# Schematic.net
KiCad netlist of a schematic drawn in EasyEDA Pro
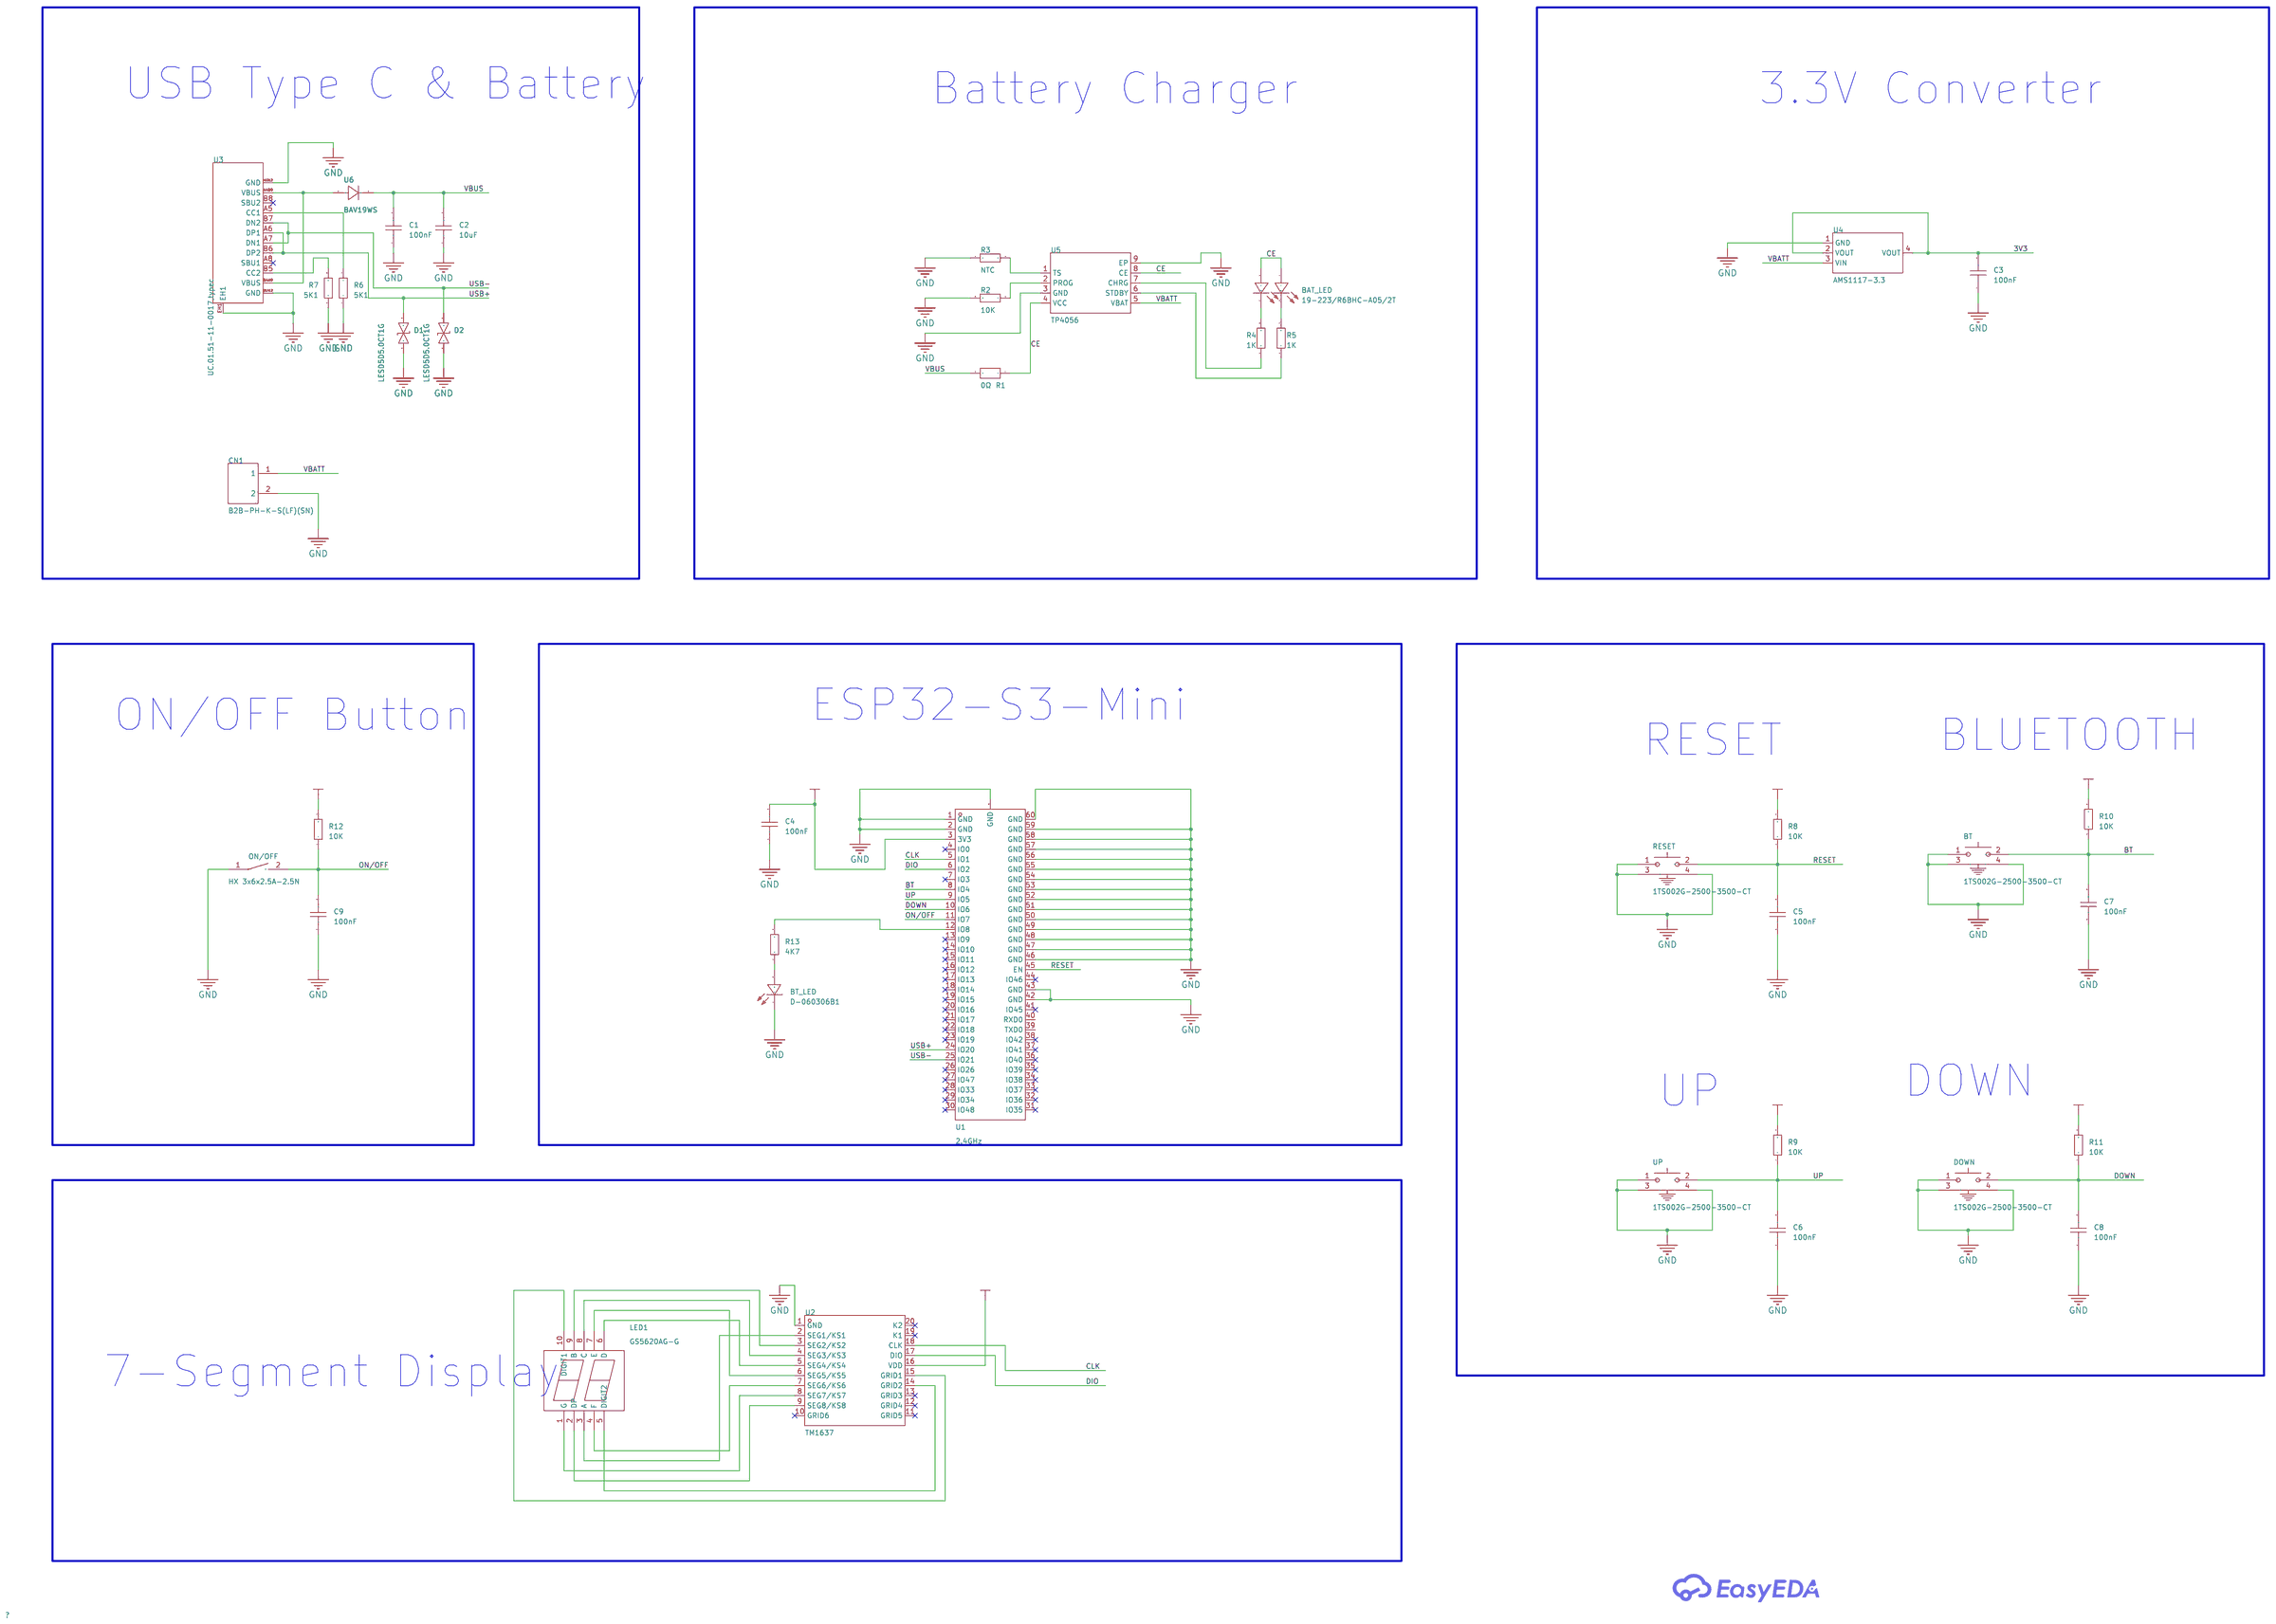
[diagram p0: schematic sheet]

(export (version "E")
  (design (tool "Eeschema 10.0.6"))
  (components
    (comp (ref "BAT_LED")
      (value "19-223/R6BHC-A05/2T")
      (footprint "easyedapro:LED-ARRAY-SMD_4P-L1.6-W1.3-BR-FD")
      (description "Emitted Color:Red,Blue")
      (fields (field (name "Manufacturer") "EVERLIGHT(亿光)"))
      (libsource (lib "easyedapro") (part "19-223/R6BHC-A05/2T"))
    )
    (comp (ref "BT")
      (value "1TS002G-2500-3500-CT")
      (footprint "easyedapro:SW-SMD_1TS002G-XXXX-3500-CT")
      (fields (field (name "Manufacturer") "HYP(鸿源精密)"))
      (libsource (lib "easyedapro") (part "1TS002G-2500-3500"))
    )
    (comp (ref "BT_LED")
      (value "D-060306B1")
      (footprint "easyedapro:LED0603-RD")
      (description "Emitted Color:Blue")
      (fields (field (name "Manufacturer") "ARKLED(方舟)"))
      (libsource (lib "easyedapro") (part "D-B060306B1-KS2"))
    )
    (comp (ref "C1")
      (value "100nF")
      (footprint "easyedapro:C0805")
      (description "Capacitance:100nF Tolerance:±10% Tolerance:±10% Voltage Rating:50V Temperature Coefficient:X7R")
      (fields
        (field (name "Manufacturer Part") "CSO0805X7R104K500KT")
        (field (name "Manufacturer") "HRE(芯声)")
      )
      (libsource (lib "easyedapro") (part "CSO0805X7R104K500KT"))
    )
    (comp (ref "C2")
      (value "10uF")
      (footprint "easyedapro:C0805")
      (description "Capacitance:10uF Tolerance:±10% Tolerance:±10% Voltage Rating:10V Temperature Coefficient:X5R")
      (fields
        (field (name "Manufacturer Part") "CL21A106KPCLQNC")
        (field (name "Manufacturer") "SAMSUNG(三星)")
      )
      (libsource (lib "easyedapro") (part "CL21A106KPCLQNC_C962097"))
    )
    (comp (ref "C3")
      (value "100nF")
      (footprint "easyedapro:C0805")
      (description "Capacitance:100nF Tolerance:±10% Tolerance:±10% Voltage Rating:50V Temperature Coefficient:X7R")
      (fields
        (field (name "Manufacturer Part") "CSO0805X7R104K500KT")
        (field (name "Manufacturer") "HRE(芯声)")
      )
      (libsource (lib "easyedapro") (part "CSO0805X7R104K500KT"))
    )
    (comp (ref "C4")
      (value "100nF")
      (footprint "easyedapro:C0805")
      (description "Capacitance:100nF Tolerance:±10% Tolerance:±10% Voltage Rating:50V Temperature Coefficient:X7R")
      (fields
        (field (name "Manufacturer Part") "CSO0805X7R104K500KT")
        (field (name "Manufacturer") "HRE(芯声)")
      )
      (libsource (lib "easyedapro") (part "CSO0805X7R104K500KT"))
    )
    (comp (ref "C5")
      (value "100nF")
      (footprint "easyedapro:C0805")
      (description "Capacitance:100nF Tolerance:±10% Tolerance:±10% Voltage Rating:50V Temperature Coefficient:X7R")
      (fields
        (field (name "Manufacturer Part") "CSO0805X7R104K500KT")
        (field (name "Manufacturer") "HRE(芯声)")
      )
      (libsource (lib "easyedapro") (part "CSO0805X7R104K500KT"))
    )
    (comp (ref "C6")
      (value "100nF")
      (footprint "easyedapro:C0805")
      (description "Capacitance:100nF Tolerance:±10% Tolerance:±10% Voltage Rating:50V Temperature Coefficient:X7R")
      (fields
        (field (name "Manufacturer Part") "CSO0805X7R104K500KT")
        (field (name "Manufacturer") "HRE(芯声)")
      )
      (libsource (lib "easyedapro") (part "CSO0805X7R104K500KT"))
    )
    (comp (ref "C7")
      (value "100nF")
      (footprint "easyedapro:C0805")
      (description "Capacitance:100nF Tolerance:±10% Tolerance:±10% Voltage Rating:50V Temperature Coefficient:X7R")
      (fields
        (field (name "Manufacturer Part") "CSO0805X7R104K500KT")
        (field (name "Manufacturer") "HRE(芯声)")
      )
      (libsource (lib "easyedapro") (part "CSO0805X7R104K500KT"))
    )
    (comp (ref "C8")
      (value "100nF")
      (footprint "easyedapro:C0805")
      (description "Capacitance:100nF Tolerance:±10% Tolerance:±10% Voltage Rating:50V Temperature Coefficient:X7R")
      (fields
        (field (name "Manufacturer Part") "CSO0805X7R104K500KT")
        (field (name "Manufacturer") "HRE(芯声)")
      )
      (libsource (lib "easyedapro") (part "CSO0805X7R104K500KT"))
    )
    (comp (ref "C9")
      (value "100nF")
      (footprint "easyedapro:C0805")
      (description "Capacitance:100nF Tolerance:±10% Tolerance:±10% Voltage Rating:50V Temperature Coefficient:X7R")
      (fields
        (field (name "Manufacturer Part") "CSO0805X7R104K500KT")
        (field (name "Manufacturer") "HRE(芯声)")
      )
      (libsource (lib "easyedapro") (part "CSO0805X7R104K500KT"))
    )
    (comp (ref "CN1")
      (value "B2B-PH-K-S(LF)(SN)")
      (footprint "easyedapro:CONN-TH_B2B-PH-K-S")
      (fields (field (name "Manufacturer") "JST"))
      (libsource (lib "easyedapro") (part "B2B-PH-K-S(LF)(SN)"))
    )
    (comp (ref "D1")
      (value "LESD5D5.0CT1G")
      (footprint "easyedapro:SOD-523_L1.2-W0.8-LS1.6-BI")
      (fields (field (name "Manufacturer") "LRC(乐山无线电)"))
      (libsource (lib "easyedapro") (part "LESD5D5.0CT1G"))
    )
    (comp (ref "D2")
      (value "LESD5D5.0CT1G")
      (footprint "easyedapro:SOD-523_L1.2-W0.8-LS1.6-BI")
      (fields (field (name "Manufacturer") "LRC(乐山无线电)"))
      (libsource (lib "easyedapro") (part "LESD5D5.0CT1G"))
    )
    (comp (ref "DOWN")
      (value "1TS002G-2500-3500-CT")
      (footprint "easyedapro:SW-SMD_1TS002G-XXXX-3500-CT")
      (fields (field (name "Manufacturer") "HYP(鸿源精密)"))
      (libsource (lib "easyedapro") (part "1TS002G-2500-3500"))
    )
    (comp (ref "LED1")
      (value "GS5620AG-G")
      (footprint "easyedapro:LED-SEG-SMD_10P-L25.1-W19.0-P2.54-S18.85-BL-1")
      (fields (field (name "Manufacturer") "Guangcai Display(光彩显示)"))
      (libsource (lib "easyedapro") (part "GS5620AG-G"))
    )
    (comp (ref "ON/OFF")
      (value "HX 3x6x2.5A-2.5N")
      (footprint "easyedapro:SW-SMD_HX-TS-1101-C-W")
      (fields (field (name "Manufacturer") "hanxia(韩下)"))
      (libsource (lib "easyedapro") (part "HX TS-1101-C-W"))
    )
    (comp (ref "R1")
      (value "0Ω")
      (footprint "easyedapro:R0603")
      (fields (field (name "Manufacturer Part") "PT0603-R-070RL") (field (name "Manufacturer") "YAGEO(国巨)"))
      (libsource (lib "easyedapro") (part "PT0603-R-070RL"))
    )
    (comp (ref "R2") (value "10K") (footprint "easyedapro:R0603") (libsource (lib "easyedapro") (part "Res")))
    (comp (ref "R3") (value "NTC") (footprint "easyedapro:R0603") (libsource (lib "easyedapro") (part "Res")))
    (comp (ref "R4") (value "1K") (footprint "easyedapro:R0603") (libsource (lib "easyedapro") (part "Res")))
    (comp (ref "R5") (value "1K") (footprint "easyedapro:R0603") (libsource (lib "easyedapro") (part "Res")))
    (comp (ref "R6") (value "5K1") (footprint "easyedapro:R0603") (libsource (lib "easyedapro") (part "Res")))
    (comp (ref "R7") (value "5K1") (footprint "easyedapro:R0603") (libsource (lib "easyedapro") (part "Res")))
    (comp (ref "R8") (value "10K") (footprint "easyedapro:R0603") (libsource (lib "easyedapro") (part "Res")))
    (comp (ref "R9") (value "10K") (footprint "easyedapro:R0603") (libsource (lib "easyedapro") (part "Res")))
    (comp (ref "R10")
      (value "10K")
      (footprint "easyedapro:R0603")
      (libsource (lib "easyedapro") (part "Res"))
    )
    (comp (ref "R11")
      (value "10K")
      (footprint "easyedapro:R0603")
      (libsource (lib "easyedapro") (part "Res"))
    )
    (comp (ref "R12")
      (value "10K")
      (footprint "easyedapro:R0603")
      (libsource (lib "easyedapro") (part "Res"))
    )
    (comp (ref "R13")
      (value "4K7")
      (footprint "easyedapro:R0603")
      (libsource (lib "easyedapro") (part "Res"))
    )
    (comp (ref "RESET")
      (value "1TS002G-2500-3500-CT")
      (footprint "easyedapro:SW-SMD_1TS002G-XXXX-3500-CT")
      (fields (field (name "Manufacturer") "HYP(鸿源精密)"))
      (libsource (lib "easyedapro") (part "1TS002G-2500-3500"))
    )
    (comp (ref "U1")
      (value "2.4GHz")
      (footprint "easyedapro:BULETM-SMD_ESP32-S3-MINI-1-N8")
      (fields
        (field (name "Manufacturer Part") "ESP32-S3-MINI-1-N8")
        (field (name "Manufacturer") "ESPRESSIF(乐鑫)")
      )
      (libsource (lib "easyedapro") (part "ESP32-S3-MINI-1-N8"))
    )
    (comp (ref "U2")
      (value "TM1637")
      (footprint "easyedapro:SOP-20_L12.8-W7.5-P1.27-LS10.4-BL")
      (fields (field (name "Manufacturer") "TM(天微)"))
      (libsource (lib "easyedapro") (part "TM1637_C2962580"))
    )
    (comp (ref "U3")
      (value "UC.01.51-11-0017,typec")
      (footprint "easyedapro:TYPE-C-SMD_UC.01.51-11-0017")
      (libsource (lib "easyedapro") (part "UC.01.51-11-0017,TYPEC"))
    )
    (comp (ref "U4")
      (value "AMS1117-3.3")
      (footprint "easyedapro:SOT-223-3_L6.5-W3.4-P2.30-LS7.0-BR")
      (fields (field (name "Manufacturer") "AMS"))
      (libsource (lib "easyedapro") (part "AMS1117-3.3"))
    )
    (comp (ref "U5")
      (value "TP4056")
      (footprint "easyedapro:ESOP-8_L4.9-W3.9-P1.27-LS6.0-BL-EP")
      (fields (field (name "Manufacturer") "JSMSEMI(杰盛微)"))
      (libsource (lib "easyedapro") (part "TP4056_C22470410"))
    )
    (comp (ref "U6")
      (value "BAV19WS")
      (footprint "easyedapro:SOD-323_L1.8-W1.3-LS2.5-RD-1")
      (fields (field (name "Manufacturer") "XZT(信展通)"))
      (libsource (lib "easyedapro") (part "BAV19WS_C5805720"))
    )
    (comp (ref "UP")
      (value "1TS002G-2500-3500-CT")
      (footprint "easyedapro:SW-SMD_1TS002G-XXXX-3500-CT")
      (fields (field (name "Manufacturer") "HYP(鸿源精密)"))
      (libsource (lib "easyedapro") (part "1TS002G-2500-3500"))
    )
  )
  (nets
    (net (code "1") (name "/BT") (class "Default")
      (node (ref "BT") (pin "2") (pinfunction "2_2") (pintype "input"))
      (node (ref "C7") (pin "2") (pinfunction "2_2") (pintype "unspecified"))
      (node (ref "R10") (pin "1") (pinfunction "1_1") (pintype "input"))
      (node (ref "U1") (pin "8") (pinfunction "IO4_8") (pintype "unspecified"))
    )
    (net (code "2") (name "/CE") (class "Default")
      (node (ref "BAT_LED") (pin "1") (pinfunction "A_1") (pintype "unspecified"))
      (node (ref "BAT_LED") (pin "3") (pinfunction "A_3") (pintype "unspecified"))
      (node (ref "R1") (pin "1") (pinfunction "1_1") (pintype "unspecified"))
      (node (ref "U5") (pin "4") (pinfunction "VCC_4") (pintype "unspecified"))
      (node (ref "U5") (pin "8") (pinfunction "CE_8") (pintype "unspecified"))
    )
    (net (code "3") (name "/CLK") (class "Default")
      (node (ref "U1") (pin "5") (pinfunction "IO1_5") (pintype "unspecified"))
      (node (ref "U2") (pin "18") (pinfunction "CLK_18") (pintype "unspecified"))
    )
    (net (code "4") (name "/DIO") (class "Default")
      (node (ref "U1") (pin "6") (pinfunction "IO2_6") (pintype "unspecified"))
      (node (ref "U2") (pin "17") (pinfunction "DIO_17") (pintype "unspecified"))
    )
    (net (code "5") (name "/DOWN") (class "Default")
      (node (ref "C8") (pin "2") (pinfunction "2_2") (pintype "unspecified"))
      (node (ref "DOWN") (pin "2") (pinfunction "2_2") (pintype "input"))
      (node (ref "R11") (pin "1") (pinfunction "1_1") (pintype "input"))
      (node (ref "U1") (pin "10") (pinfunction "IO6_10") (pintype "unspecified"))
    )
    (net (code "6") (name "/ON{slash}OFF") (class "Default")
      (node (ref "C9") (pin "2") (pinfunction "2_2") (pintype "unspecified"))
      (node (ref "ON/OFF") (pin "2") (pinfunction "2_2") (pintype "unspecified"))
      (node (ref "R12") (pin "1") (pinfunction "1_1") (pintype "input"))
      (node (ref "U1") (pin "11") (pinfunction "IO7_11") (pintype "unspecified"))
    )
    (net (code "7") (name "/RESET") (class "Default")
      (node (ref "C5") (pin "2") (pinfunction "2_2") (pintype "unspecified"))
      (node (ref "R8") (pin "1") (pinfunction "1_1") (pintype "input"))
      (node (ref "RESET") (pin "2") (pinfunction "2_2") (pintype "input"))
      (node (ref "U1") (pin "45") (pinfunction "EN_45") (pintype "unspecified"))
    )
    (net (code "8") (name "/UP") (class "Default")
      (node (ref "C6") (pin "2") (pinfunction "2_2") (pintype "unspecified"))
      (node (ref "R9") (pin "1") (pinfunction "1_1") (pintype "input"))
      (node (ref "U1") (pin "9") (pinfunction "IO5_9") (pintype "unspecified"))
      (node (ref "UP") (pin "2") (pinfunction "2_2") (pintype "input"))
    )
    (net (code "9") (name "/USB+") (class "Default")
      (node (ref "D1") (pin "2") (pinfunction "2_2") (pintype "unspecified"))
      (node (ref "U1") (pin "24") (pinfunction "IO20_24") (pintype "unspecified"))
      (node (ref "U3") (pin "A6") (pinfunction "DP1_A6") (pintype "unspecified"))
      (node (ref "U3") (pin "B6") (pinfunction "DP2_B6") (pintype "unspecified"))
    )
    (net (code "10") (name "/USB-") (class "Default")
      (node (ref "D2") (pin "2") (pinfunction "2_2") (pintype "unspecified"))
      (node (ref "U1") (pin "25") (pinfunction "IO21_25") (pintype "unspecified"))
      (node (ref "U3") (pin "A7") (pinfunction "DN1_A7") (pintype "unspecified"))
      (node (ref "U3") (pin "B7") (pinfunction "DN2_B7") (pintype "unspecified"))
    )
    (net (code "11") (name "/VBUS") (class "Default")
      (node (ref "C1") (pin "2") (pinfunction "2_2") (pintype "unspecified"))
      (node (ref "C2") (pin "2") (pinfunction "2_2") (pintype "unspecified"))
      (node (ref "R1") (pin "2") (pinfunction "2_2") (pintype "unspecified"))
      (node (ref "U6") (pin "1") (pinfunction "K_1") (pintype "unspecified"))
    )
    (net (code "12") (name "3V3") (class "Default")
      (node (ref "C3") (pin "2") (pinfunction "2_2") (pintype "unspecified"))
      (node (ref "C4") (pin "2") (pinfunction "2_2") (pintype "unspecified"))
      (node (ref "R10") (pin "2") (pinfunction "2_2") (pintype "input"))
      (node (ref "R11") (pin "2") (pinfunction "2_2") (pintype "input"))
      (node (ref "R12") (pin "2") (pinfunction "2_2") (pintype "input"))
      (node (ref "R8") (pin "2") (pinfunction "2_2") (pintype "input"))
      (node (ref "R9") (pin "2") (pinfunction "2_2") (pintype "input"))
      (node (ref "U1") (pin "3") (pinfunction "3V3_3") (pintype "unspecified"))
      (node (ref "U4") (pin "2") (pinfunction "VOUT_2") (pintype "unspecified"))
      (node (ref "U4") (pin "4") (pinfunction "VOUT_4") (pintype "unspecified"))
    )
    (net (code "13") (name "GND") (class "Default")
      (node (ref "BT") (pin "1") (pinfunction "1_1") (pintype "input"))
      (node (ref "BT") (pin "3") (pinfunction "3_3") (pintype "input"))
      (node (ref "BT") (pin "4") (pinfunction "4_4") (pintype "input"))
      (node (ref "BT_LED") (pin "1") (pinfunction "1_1") (pintype "unspecified"))
      (node (ref "C1") (pin "1") (pinfunction "1_1") (pintype "unspecified"))
      (node (ref "C2") (pin "1") (pinfunction "1_1") (pintype "unspecified"))
      (node (ref "C3") (pin "1") (pinfunction "1_1") (pintype "unspecified"))
      (node (ref "C4") (pin "1") (pinfunction "1_1") (pintype "unspecified"))
      (node (ref "C5") (pin "1") (pinfunction "1_1") (pintype "unspecified"))
      (node (ref "C6") (pin "1") (pinfunction "1_1") (pintype "unspecified"))
      (node (ref "C7") (pin "1") (pinfunction "1_1") (pintype "unspecified"))
      (node (ref "C8") (pin "1") (pinfunction "1_1") (pintype "unspecified"))
      (node (ref "C9") (pin "1") (pinfunction "1_1") (pintype "unspecified"))
      (node (ref "CN1") (pin "2") (pinfunction "2_2") (pintype "input"))
      (node (ref "D1") (pin "1") (pinfunction "1_1") (pintype "unspecified"))
      (node (ref "D2") (pin "1") (pinfunction "1_1") (pintype "unspecified"))
      (node (ref "DOWN") (pin "1") (pinfunction "1_1") (pintype "input"))
      (node (ref "DOWN") (pin "3") (pinfunction "3_3") (pintype "input"))
      (node (ref "DOWN") (pin "4") (pinfunction "4_4") (pintype "input"))
      (node (ref "ON/OFF") (pin "1") (pinfunction "1_1") (pintype "unspecified"))
      (node (ref "R2") (pin "2") (pinfunction "2_2") (pintype "input"))
      (node (ref "R3") (pin "1") (pinfunction "1_1") (pintype "input"))
      (node (ref "R6") (pin "1") (pinfunction "1_1") (pintype "input"))
      (node (ref "R7") (pin "1") (pinfunction "1_1") (pintype "input"))
      (node (ref "RESET") (pin "1") (pinfunction "1_1") (pintype "input"))
      (node (ref "RESET") (pin "3") (pinfunction "3_3") (pintype "input"))
      (node (ref "RESET") (pin "4") (pinfunction "4_4") (pintype "input"))
      (node (ref "U1") (pin "1") (pinfunction "GND_1") (pintype "unspecified"))
      (node (ref "U1") (pin "2") (pinfunction "GND_2") (pintype "unspecified"))
      (node (ref "U1") (pin "42") (pinfunction "GND_42") (pintype "unspecified"))
      (node (ref "U1") (pin "43") (pinfunction "GND_43") (pintype "unspecified"))
      (node (ref "U1") (pin "46") (pinfunction "GND_46") (pintype "unspecified"))
      (node (ref "U1") (pin "47") (pinfunction "GND_47") (pintype "unspecified"))
      (node (ref "U1") (pin "48") (pinfunction "GND_48") (pintype "unspecified"))
      (node (ref "U1") (pin "49") (pinfunction "GND_49") (pintype "unspecified"))
      (node (ref "U1") (pin "50") (pinfunction "GND_50") (pintype "unspecified"))
      (node (ref "U1") (pin "51") (pinfunction "GND_51") (pintype "unspecified"))
      (node (ref "U1") (pin "52") (pinfunction "GND_52") (pintype "unspecified"))
      (node (ref "U1") (pin "53") (pinfunction "GND_53") (pintype "unspecified"))
      (node (ref "U1") (pin "54") (pinfunction "GND_54") (pintype "unspecified"))
      (node (ref "U1") (pin "55") (pinfunction "GND_55") (pintype "unspecified"))
      (node (ref "U1") (pin "56") (pinfunction "GND_56") (pintype "unspecified"))
      (node (ref "U1") (pin "57") (pinfunction "GND_57") (pintype "unspecified"))
      (node (ref "U1") (pin "58") (pinfunction "GND_58") (pintype "unspecified"))
      (node (ref "U1") (pin "59") (pinfunction "GND_59") (pintype "unspecified"))
      (node (ref "U1") (pin "60") (pinfunction "GND_60") (pintype "unspecified"))
      (node (ref "U1") (pin "GND") (pinfunction "GND_GND") (pintype "unspecified"))
      (node (ref "U2") (pin "1") (pinfunction "GND_1") (pintype "unspecified"))
      (node (ref "U3") (pin "A1B12") (pinfunction "GND_A1B12") (pintype "unspecified"))
      (node (ref "U3") (pin "B1A12") (pinfunction "GND_B1A12") (pintype "unspecified"))
      (node (ref "U3") (pin "EH1") (pinfunction "EH1_EH1") (pintype "unspecified"))
      (node (ref "U4") (pin "1") (pinfunction "GND_1") (pintype "unspecified"))
      (node (ref "U5") (pin "3") (pinfunction "GND_3") (pintype "unspecified"))
      (node (ref "U5") (pin "9") (pinfunction "EP_9") (pintype "unspecified"))
      (node (ref "UP") (pin "1") (pinfunction "1_1") (pintype "input"))
      (node (ref "UP") (pin "3") (pinfunction "3_3") (pintype "input"))
      (node (ref "UP") (pin "4") (pinfunction "4_4") (pintype "input"))
    )
    (net (code "14") (name "Net-(BAT_LED-C-Pad2)") (class "Default")
      (node (ref "BAT_LED") (pin "2") (pinfunction "C_2") (pintype "unspecified"))
      (node (ref "R5") (pin "2") (pinfunction "2_2") (pintype "input"))
    )
    (net (code "15") (name "Net-(BAT_LED-C-Pad4)") (class "Default")
      (node (ref "BAT_LED") (pin "4") (pinfunction "C_4") (pintype "unspecified"))
      (node (ref "R4") (pin "2") (pinfunction "2_2") (pintype "input"))
    )
    (net (code "16") (name "Net-(BT_LED-Pad2)") (class "Default")
      (node (ref "BT_LED") (pin "2") (pinfunction "2_2") (pintype "unspecified"))
      (node (ref "R13") (pin "1") (pinfunction "1_1") (pintype "input"))
    )
    (net (code "17") (name "Net-(LED1-A)") (class "Default")
      (node (ref "LED1") (pin "3") (pinfunction "A_3") (pintype "unspecified"))
      (node (ref "U2") (pin "2") (pinfunction "SEG1/KS1_2") (pintype "unspecified"))
    )
    (net (code "18") (name "Net-(LED1-B)") (class "Default")
      (node (ref "LED1") (pin "9") (pinfunction "B_9") (pintype "unspecified"))
      (node (ref "U2") (pin "3") (pinfunction "SEG2/KS2_3") (pintype "unspecified"))
    )
    (net (code "19") (name "Net-(LED1-C)") (class "Default")
      (node (ref "LED1") (pin "8") (pinfunction "C_8") (pintype "unspecified"))
      (node (ref "U2") (pin "4") (pinfunction "SEG3/KS3_4") (pintype "unspecified"))
    )
    (net (code "20") (name "Net-(LED1-D)") (class "Default")
      (node (ref "LED1") (pin "6") (pinfunction "D_6") (pintype "unspecified"))
      (node (ref "U2") (pin "5") (pinfunction "SEG4/KS4_5") (pintype "unspecified"))
    )
    (net (code "21") (name "Net-(LED1-DIGIT1)") (class "Default")
      (node (ref "LED1") (pin "10") (pinfunction "DIGIT1_10") (pintype "unspecified"))
      (node (ref "U2") (pin "15") (pinfunction "GRID1_15") (pintype "unspecified"))
    )
    (net (code "22") (name "Net-(LED1-DIGIT2)") (class "Default")
      (node (ref "LED1") (pin "5") (pinfunction "DIGIT2_5") (pintype "unspecified"))
      (node (ref "U2") (pin "14") (pinfunction "GRID2_14") (pintype "unspecified"))
    )
    (net (code "23") (name "Net-(LED1-DP)") (class "Default")
      (node (ref "LED1") (pin "2") (pinfunction "DP_2") (pintype "unspecified"))
      (node (ref "U2") (pin "9") (pinfunction "SEG8/KS8_9") (pintype "unspecified"))
    )
    (net (code "24") (name "Net-(LED1-E)") (class "Default")
      (node (ref "LED1") (pin "7") (pinfunction "E_7") (pintype "unspecified"))
      (node (ref "U2") (pin "6") (pinfunction "SEG5/KS5_6") (pintype "unspecified"))
    )
    (net (code "25") (name "Net-(LED1-F)") (class "Default")
      (node (ref "LED1") (pin "4") (pinfunction "F_4") (pintype "unspecified"))
      (node (ref "U2") (pin "7") (pinfunction "SEG6/KS6_7") (pintype "unspecified"))
    )
    (net (code "26") (name "Net-(LED1-G)") (class "Default")
      (node (ref "LED1") (pin "1") (pinfunction "G_1") (pintype "unspecified"))
      (node (ref "U2") (pin "8") (pinfunction "SEG7/KS7_8") (pintype "unspecified"))
    )
    (net (code "27") (name "Net-(U1-IO8)") (class "Default")
      (node (ref "R13") (pin "2") (pinfunction "2_2") (pintype "input"))
      (node (ref "U1") (pin "12") (pinfunction "IO8_12") (pintype "unspecified"))
    )
    (net (code "28") (name "Net-(U3-CC1)") (class "Default")
      (node (ref "R6") (pin "2") (pinfunction "2_2") (pintype "input"))
      (node (ref "U3") (pin "A5") (pinfunction "CC1_A5") (pintype "unspecified"))
    )
    (net (code "29") (name "Net-(U3-CC2)") (class "Default")
      (node (ref "R7") (pin "2") (pinfunction "2_2") (pintype "input"))
      (node (ref "U3") (pin "B5") (pinfunction "CC2_B5") (pintype "unspecified"))
    )
    (net (code "30") (name "Net-(U5-CHRG)") (class "Default")
      (node (ref "R4") (pin "1") (pinfunction "1_1") (pintype "input"))
      (node (ref "U5") (pin "7") (pinfunction "CHRG_7") (pintype "unspecified"))
    )
    (net (code "31") (name "Net-(U5-PROG)") (class "Default")
      (node (ref "R2") (pin "1") (pinfunction "1_1") (pintype "input"))
      (node (ref "U5") (pin "2") (pinfunction "PROG_2") (pintype "unspecified"))
    )
    (net (code "32") (name "Net-(U5-STDBY)") (class "Default")
      (node (ref "R5") (pin "1") (pinfunction "1_1") (pintype "input"))
      (node (ref "U5") (pin "6") (pinfunction "STDBY_6") (pintype "unspecified"))
    )
    (net (code "33") (name "Net-(U5-TS)") (class "Default")
      (node (ref "R3") (pin "2") (pinfunction "2_2") (pintype "input"))
      (node (ref "U5") (pin "1") (pinfunction "TS_1") (pintype "unspecified"))
    )
    (net (code "34") (name "Net-(U6-A)") (class "Default")
      (node (ref "U3") (pin "A4B9") (pinfunction "VBUS_A4B9") (pintype "unspecified"))
      (node (ref "U3") (pin "B4A9") (pinfunction "VBUS_B4A9") (pintype "unspecified"))
      (node (ref "U6") (pin "2") (pinfunction "A_2") (pintype "unspecified"))
    )
    (net (code "35") (name "VBATT") (class "Default")
      (node (ref "CN1") (pin "1") (pinfunction "1_1") (pintype "input"))
      (node (ref "U2") (pin "16") (pinfunction "VDD_16") (pintype "unspecified"))
      (node (ref "U4") (pin "3") (pinfunction "VIN_3") (pintype "unspecified"))
      (node (ref "U5") (pin "5") (pinfunction "VBAT_5") (pintype "unspecified"))
    )
    (net (code "36") (name "unconnected-(U1-IO0-Pad4)") (class "Default")
      (node (ref "U1") (pin "4") (pinfunction "IO0_4") (pintype "unspecified+no_connect"))
    )
    (net (code "37") (name "unconnected-(U1-IO3-Pad7)") (class "Default")
      (node (ref "U1") (pin "7") (pinfunction "IO3_7") (pintype "unspecified+no_connect"))
    )
    (net (code "38") (name "unconnected-(U1-IO9-Pad13)") (class "Default")
      (node (ref "U1") (pin "13") (pinfunction "IO9_13") (pintype "unspecified+no_connect"))
    )
    (net (code "39") (name "unconnected-(U1-IO10-Pad14)") (class "Default")
      (node (ref "U1") (pin "14") (pinfunction "IO10_14") (pintype "unspecified+no_connect"))
    )
    (net (code "40") (name "unconnected-(U1-IO11-Pad15)") (class "Default")
      (node (ref "U1") (pin "15") (pinfunction "IO11_15") (pintype "unspecified+no_connect"))
    )
    (net (code "41") (name "unconnected-(U1-IO12-Pad16)") (class "Default")
      (node (ref "U1") (pin "16") (pinfunction "IO12_16") (pintype "unspecified+no_connect"))
    )
    (net (code "42") (name "unconnected-(U1-IO13-Pad17)") (class "Default")
      (node (ref "U1") (pin "17") (pinfunction "IO13_17") (pintype "unspecified+no_connect"))
    )
    (net (code "43") (name "unconnected-(U1-IO14-Pad18)") (class "Default")
      (node (ref "U1") (pin "18") (pinfunction "IO14_18") (pintype "unspecified+no_connect"))
    )
    (net (code "44") (name "unconnected-(U1-IO15-Pad19)") (class "Default")
      (node (ref "U1") (pin "19") (pinfunction "IO15_19") (pintype "unspecified+no_connect"))
    )
    (net (code "45") (name "unconnected-(U1-IO16-Pad20)") (class "Default")
      (node (ref "U1") (pin "20") (pinfunction "IO16_20") (pintype "unspecified+no_connect"))
    )
    (net (code "46") (name "unconnected-(U1-IO17-Pad21)") (class "Default")
      (node (ref "U1") (pin "21") (pinfunction "IO17_21") (pintype "unspecified+no_connect"))
    )
    (net (code "47") (name "unconnected-(U1-IO18-Pad22)") (class "Default")
      (node (ref "U1") (pin "22") (pinfunction "IO18_22") (pintype "unspecified+no_connect"))
    )
    (net (code "48") (name "unconnected-(U1-IO19-Pad23)") (class "Default")
      (node (ref "U1") (pin "23") (pinfunction "IO19_23") (pintype "unspecified+no_connect"))
    )
    (net (code "49") (name "unconnected-(U1-IO26-Pad26)") (class "Default")
      (node (ref "U1") (pin "26") (pinfunction "IO26_26") (pintype "unspecified+no_connect"))
    )
    (net (code "50") (name "unconnected-(U1-IO33-Pad28)") (class "Default")
      (node (ref "U1") (pin "28") (pinfunction "IO33_28") (pintype "unspecified+no_connect"))
    )
    (net (code "51") (name "unconnected-(U1-IO34-Pad29)") (class "Default")
      (node (ref "U1") (pin "29") (pinfunction "IO34_29") (pintype "unspecified+no_connect"))
    )
    (net (code "52") (name "unconnected-(U1-IO35-Pad31)") (class "Default")
      (node (ref "U1") (pin "31") (pinfunction "IO35_31") (pintype "unspecified+no_connect"))
    )
    (net (code "53") (name "unconnected-(U1-IO36-Pad32)") (class "Default")
      (node (ref "U1") (pin "32") (pinfunction "IO36_32") (pintype "unspecified+no_connect"))
    )
    (net (code "54") (name "unconnected-(U1-IO37-Pad33)") (class "Default")
      (node (ref "U1") (pin "33") (pinfunction "IO37_33") (pintype "unspecified+no_connect"))
    )
    (net (code "55") (name "unconnected-(U1-IO38-Pad34)") (class "Default")
      (node (ref "U1") (pin "34") (pinfunction "IO38_34") (pintype "unspecified+no_connect"))
    )
    (net (code "56") (name "unconnected-(U1-IO39-Pad35)") (class "Default")
      (node (ref "U1") (pin "35") (pinfunction "IO39_35") (pintype "unspecified+no_connect"))
    )
    (net (code "57") (name "unconnected-(U1-IO40-Pad36)") (class "Default")
      (node (ref "U1") (pin "36") (pinfunction "IO40_36") (pintype "unspecified+no_connect"))
    )
    (net (code "58") (name "unconnected-(U1-IO41-Pad37)") (class "Default")
      (node (ref "U1") (pin "37") (pinfunction "IO41_37") (pintype "unspecified+no_connect"))
    )
    (net (code "59") (name "unconnected-(U1-IO42-Pad38)") (class "Default")
      (node (ref "U1") (pin "38") (pinfunction "IO42_38") (pintype "unspecified+no_connect"))
    )
    (net (code "60") (name "unconnected-(U1-IO45-Pad41)") (class "Default")
      (node (ref "U1") (pin "41") (pinfunction "IO45_41") (pintype "unspecified+no_connect"))
    )
    (net (code "61") (name "unconnected-(U1-IO46-Pad44)") (class "Default")
      (node (ref "U1") (pin "44") (pinfunction "IO46_44") (pintype "unspecified+no_connect"))
    )
    (net (code "62") (name "unconnected-(U1-IO47-Pad27)") (class "Default")
      (node (ref "U1") (pin "27") (pinfunction "IO47_27") (pintype "unspecified+no_connect"))
    )
    (net (code "63") (name "unconnected-(U1-IO48-Pad30)") (class "Default")
      (node (ref "U1") (pin "30") (pinfunction "IO48_30") (pintype "unspecified+no_connect"))
    )
    (net (code "64") (name "unconnected-(U1-RXD0-Pad40)") (class "Default")
      (node (ref "U1") (pin "40") (pinfunction "RXD0_40") (pintype "unspecified"))
    )
    (net (code "65") (name "unconnected-(U1-TXD0-Pad39)") (class "Default")
      (node (ref "U1") (pin "39") (pinfunction "TXD0_39") (pintype "unspecified"))
    )
    (net (code "66") (name "unconnected-(U2-GRID3-Pad13)") (class "Default")
      (node (ref "U2") (pin "13") (pinfunction "GRID3_13") (pintype "unspecified+no_connect"))
    )
    (net (code "67") (name "unconnected-(U2-GRID4-Pad12)") (class "Default")
      (node (ref "U2") (pin "12") (pinfunction "GRID4_12") (pintype "unspecified+no_connect"))
    )
    (net (code "68") (name "unconnected-(U2-GRID5-Pad11)") (class "Default")
      (node (ref "U2") (pin "11") (pinfunction "GRID5_11") (pintype "unspecified+no_connect"))
    )
    (net (code "69") (name "unconnected-(U2-GRID6-Pad10)") (class "Default")
      (node (ref "U2") (pin "10") (pinfunction "GRID6_10") (pintype "unspecified+no_connect"))
    )
    (net (code "70") (name "unconnected-(U2-K1-Pad19)") (class "Default")
      (node (ref "U2") (pin "19") (pinfunction "K1_19") (pintype "unspecified+no_connect"))
    )
    (net (code "71") (name "unconnected-(U2-K2-Pad20)") (class "Default")
      (node (ref "U2") (pin "20") (pinfunction "K2_20") (pintype "unspecified+no_connect"))
    )
    (net (code "72") (name "unconnected-(U3-SBU1-PadA8)") (class "Default")
      (node (ref "U3") (pin "A8") (pinfunction "SBU1_A8") (pintype "unspecified+no_connect"))
    )
    (net (code "73") (name "unconnected-(U3-SBU2-PadB8)") (class "Default")
      (node (ref "U3") (pin "B8") (pinfunction "SBU2_B8") (pintype "unspecified+no_connect"))
    )
  )
)
